# LilyPad_LED_5pcs.net
KiCad netlist of a schematic drawn in EAGLE
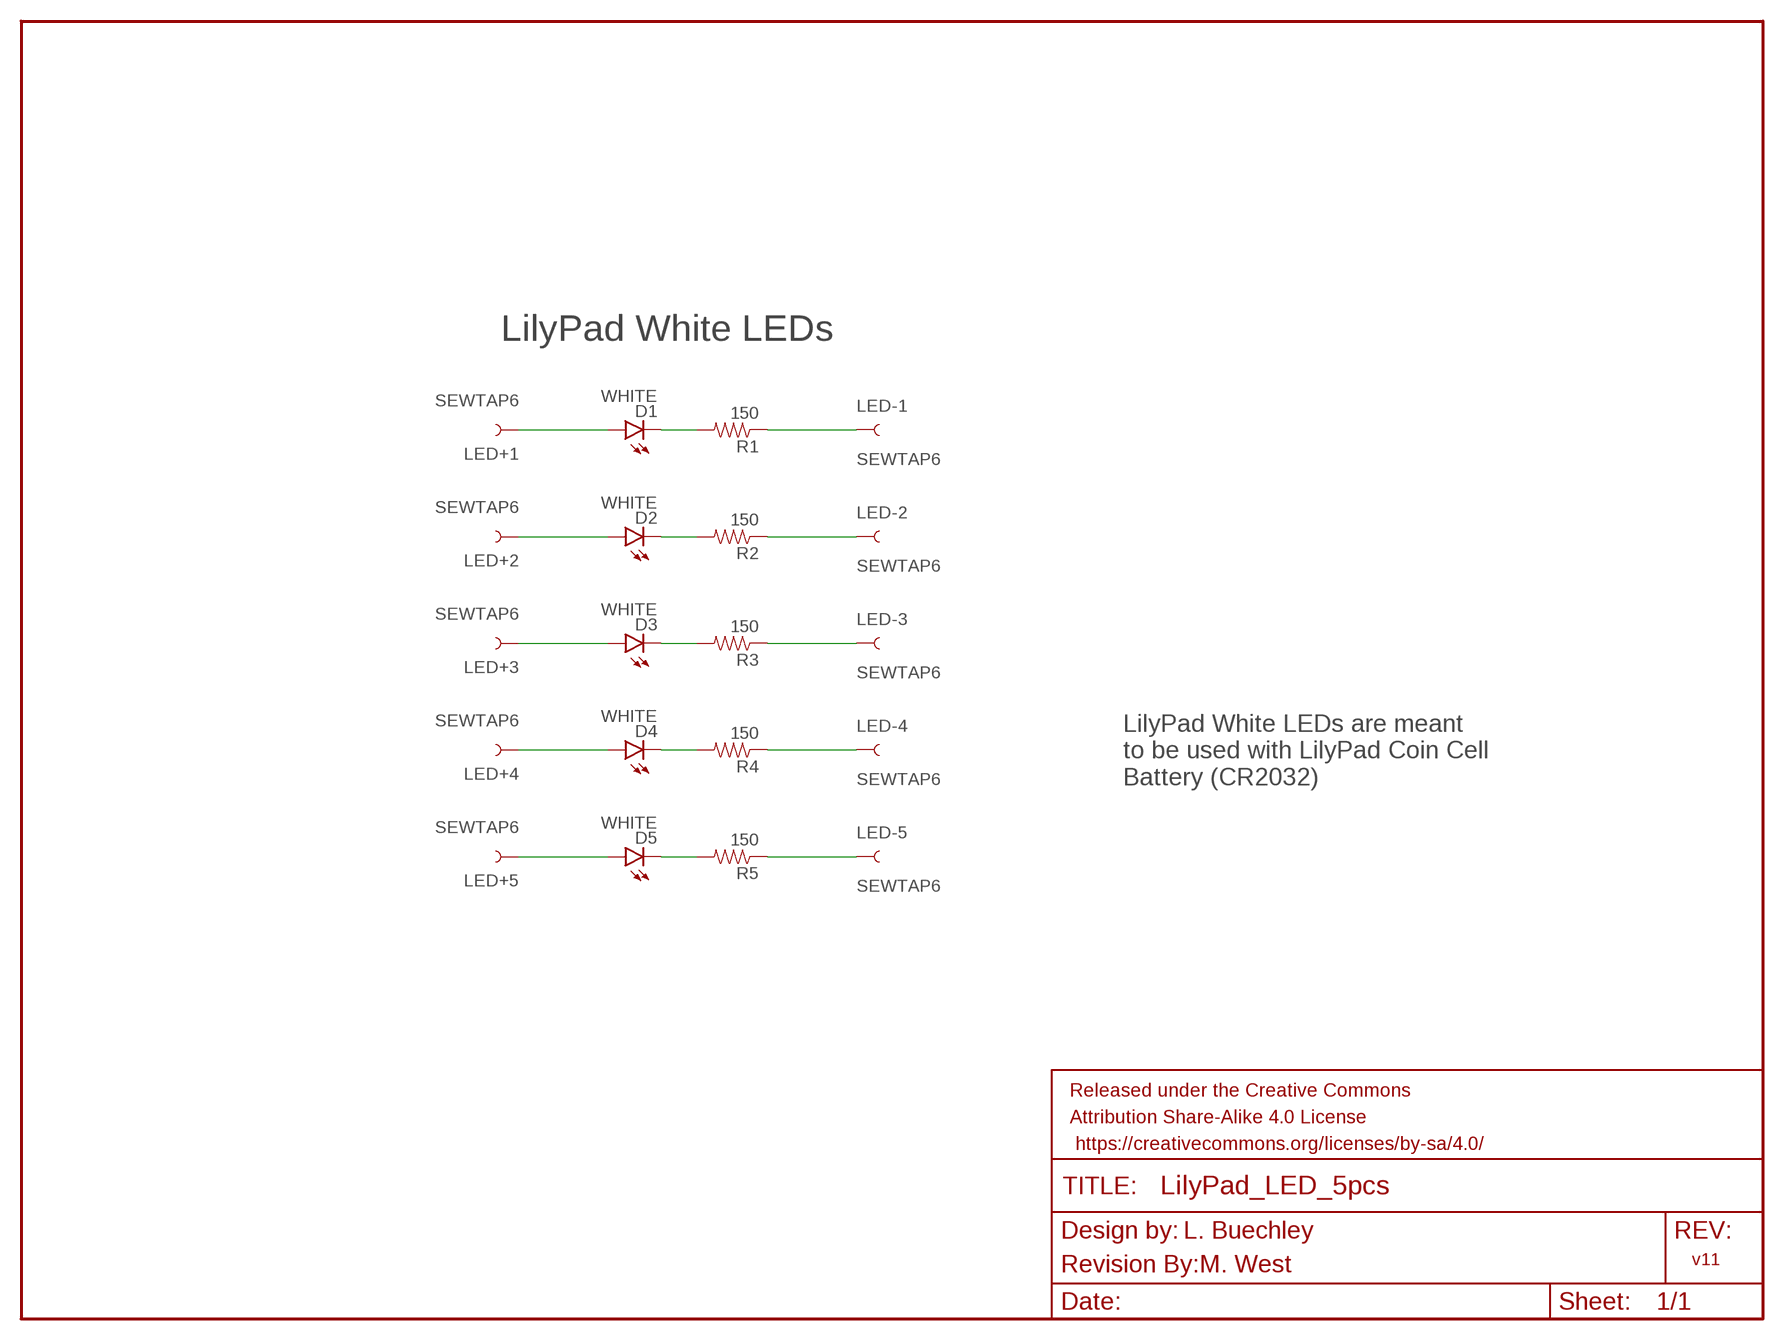
[diagram p0: schematic, sheet 1]

(export (version "E")
  (design (tool "Eeschema 10.0.6"))
  (components
    (comp (ref "D1")
      (value "WHITE")
      (footprint "eagle-import:LED-1206")
      (libsource (lib "eagle-import") (part "LED-WHITE1206"))
    )
    (comp (ref "D2")
      (value "WHITE")
      (footprint "eagle-import:LED-1206")
      (libsource (lib "eagle-import") (part "LED-WHITE1206"))
    )
    (comp (ref "D3")
      (value "WHITE")
      (footprint "eagle-import:LED-1206")
      (libsource (lib "eagle-import") (part "LED-WHITE1206"))
    )
    (comp (ref "D4")
      (value "WHITE")
      (footprint "eagle-import:LED-1206")
      (libsource (lib "eagle-import") (part "LED-WHITE1206"))
    )
    (comp (ref "D5")
      (value "WHITE")
      (footprint "eagle-import:LED-1206")
      (libsource (lib "eagle-import") (part "LED-WHITE1206"))
    )
    (comp (ref "FRAME1")
      (value "FRAME-LETTER")
      (footprint "eagle-import:CREATIVE_COMMONS")
      (libsource (lib "eagle-import") (part "FRAME-LETTER"))
    )
    (comp (ref "LED+1")
      (value "SEWTAP6")
      (footprint "eagle-import:PETAL-SMALL-2SIDE")
      (libsource (lib "eagle-import") (part "SEWTAP6"))
    )
    (comp (ref "LED+2")
      (value "SEWTAP6")
      (footprint "eagle-import:PETAL-SMALL-2SIDE")
      (libsource (lib "eagle-import") (part "SEWTAP6"))
    )
    (comp (ref "LED+3")
      (value "SEWTAP6")
      (footprint "eagle-import:PETAL-SMALL-2SIDE")
      (libsource (lib "eagle-import") (part "SEWTAP6"))
    )
    (comp (ref "LED+4")
      (value "SEWTAP6")
      (footprint "eagle-import:PETAL-SMALL-2SIDE")
      (libsource (lib "eagle-import") (part "SEWTAP6"))
    )
    (comp (ref "LED+5")
      (value "SEWTAP6")
      (footprint "eagle-import:PETAL-SMALL-2SIDE")
      (libsource (lib "eagle-import") (part "SEWTAP6"))
    )
    (comp (ref "LED-1")
      (value "SEWTAP6")
      (footprint "eagle-import:PETAL-SMALL-2SIDE")
      (libsource (lib "eagle-import") (part "SEWTAP6"))
    )
    (comp (ref "LED-2")
      (value "SEWTAP6")
      (footprint "eagle-import:PETAL-SMALL-2SIDE")
      (libsource (lib "eagle-import") (part "SEWTAP6"))
    )
    (comp (ref "LED-3")
      (value "SEWTAP6")
      (footprint "eagle-import:PETAL-SMALL-2SIDE")
      (libsource (lib "eagle-import") (part "SEWTAP6"))
    )
    (comp (ref "LED-4")
      (value "SEWTAP6")
      (footprint "eagle-import:PETAL-SMALL-2SIDE")
      (libsource (lib "eagle-import") (part "SEWTAP6"))
    )
    (comp (ref "LED-5")
      (value "SEWTAP6")
      (footprint "eagle-import:PETAL-SMALL-2SIDE")
      (libsource (lib "eagle-import") (part "SEWTAP6"))
    )
    (comp (ref "R1")
      (value "150")
      (footprint "eagle-import:0603-RES")
      (libsource (lib "eagle-import") (part "150OHM-1/10W-1%(0603)"))
    )
    (comp (ref "R2")
      (value "150")
      (footprint "eagle-import:0603-RES")
      (libsource (lib "eagle-import") (part "150OHM-1/10W-1%(0603)"))
    )
    (comp (ref "R3")
      (value "150")
      (footprint "eagle-import:0603-RES")
      (libsource (lib "eagle-import") (part "150OHM-1/10W-1%(0603)"))
    )
    (comp (ref "R4")
      (value "150")
      (footprint "eagle-import:0603-RES")
      (libsource (lib "eagle-import") (part "150OHM-1/10W-1%(0603)"))
    )
    (comp (ref "R5")
      (value "150")
      (footprint "eagle-import:0603-RES")
      (libsource (lib "eagle-import") (part "150OHM-1/10W-1%(0603)"))
    )
    (comp (ref "U$6")
      (value "REVISION")
      (footprint "eagle-import:REVISION")
      (libsource (lib "eagle-import") (part "REVISION"))
    )
  )
  (nets
    (net (code "1") (name "Net-(D1-PadA)") (class "Default")
      (node (ref "D1") (pin "A") (pinfunction "A_A") (pintype "passive"))
      (node (ref "LED+1") (pin "1") (pinfunction "1_1") (pintype "bidirectional"))
    )
    (net (code "2") (name "Net-(D1-PadC)") (class "Default")
      (node (ref "D1") (pin "C") (pinfunction "C_C") (pintype "passive"))
      (node (ref "R1") (pin "2") (pinfunction "2_2") (pintype "passive"))
    )
    (net (code "3") (name "Net-(D2-PadA)") (class "Default")
      (node (ref "D2") (pin "A") (pinfunction "A_A") (pintype "passive"))
      (node (ref "LED+2") (pin "1") (pinfunction "1_1") (pintype "bidirectional"))
    )
    (net (code "4") (name "Net-(D2-PadC)") (class "Default")
      (node (ref "D2") (pin "C") (pinfunction "C_C") (pintype "passive"))
      (node (ref "R2") (pin "2") (pinfunction "2_2") (pintype "passive"))
    )
    (net (code "5") (name "Net-(D3-PadA)") (class "Default")
      (node (ref "D3") (pin "A") (pinfunction "A_A") (pintype "passive"))
      (node (ref "LED+3") (pin "1") (pinfunction "1_1") (pintype "bidirectional"))
    )
    (net (code "6") (name "Net-(D3-PadC)") (class "Default")
      (node (ref "D3") (pin "C") (pinfunction "C_C") (pintype "passive"))
      (node (ref "R3") (pin "2") (pinfunction "2_2") (pintype "passive"))
    )
    (net (code "7") (name "Net-(D4-PadA)") (class "Default")
      (node (ref "D4") (pin "A") (pinfunction "A_A") (pintype "passive"))
      (node (ref "LED+4") (pin "1") (pinfunction "1_1") (pintype "bidirectional"))
    )
    (net (code "8") (name "Net-(D4-PadC)") (class "Default")
      (node (ref "D4") (pin "C") (pinfunction "C_C") (pintype "passive"))
      (node (ref "R4") (pin "2") (pinfunction "2_2") (pintype "passive"))
    )
    (net (code "9") (name "Net-(D5-PadA)") (class "Default")
      (node (ref "D5") (pin "A") (pinfunction "A_A") (pintype "passive"))
      (node (ref "LED+5") (pin "1") (pinfunction "1_1") (pintype "bidirectional"))
    )
    (net (code "10") (name "Net-(D5-PadC)") (class "Default")
      (node (ref "D5") (pin "C") (pinfunction "C_C") (pintype "passive"))
      (node (ref "R5") (pin "2") (pinfunction "2_2") (pintype "passive"))
    )
    (net (code "11") (name "Net-(LED-1-Pad1)") (class "Default")
      (node (ref "LED-1") (pin "1") (pinfunction "1_1") (pintype "bidirectional"))
      (node (ref "R1") (pin "1") (pinfunction "1_1") (pintype "passive"))
    )
    (net (code "12") (name "Net-(LED-2-Pad1)") (class "Default")
      (node (ref "LED-2") (pin "1") (pinfunction "1_1") (pintype "bidirectional"))
      (node (ref "R2") (pin "1") (pinfunction "1_1") (pintype "passive"))
    )
    (net (code "13") (name "Net-(LED-3-Pad1)") (class "Default")
      (node (ref "LED-3") (pin "1") (pinfunction "1_1") (pintype "bidirectional"))
      (node (ref "R3") (pin "1") (pinfunction "1_1") (pintype "passive"))
    )
    (net (code "14") (name "Net-(LED-4-Pad1)") (class "Default")
      (node (ref "LED-4") (pin "1") (pinfunction "1_1") (pintype "bidirectional"))
      (node (ref "R4") (pin "1") (pinfunction "1_1") (pintype "passive"))
    )
    (net (code "15") (name "Net-(LED-5-Pad1)") (class "Default")
      (node (ref "LED-5") (pin "1") (pinfunction "1_1") (pintype "bidirectional"))
      (node (ref "R5") (pin "1") (pinfunction "1_1") (pintype "passive"))
    )
  )
)
